# MCU.net
KiCad netlist of a schematic drawn in Altium Designer
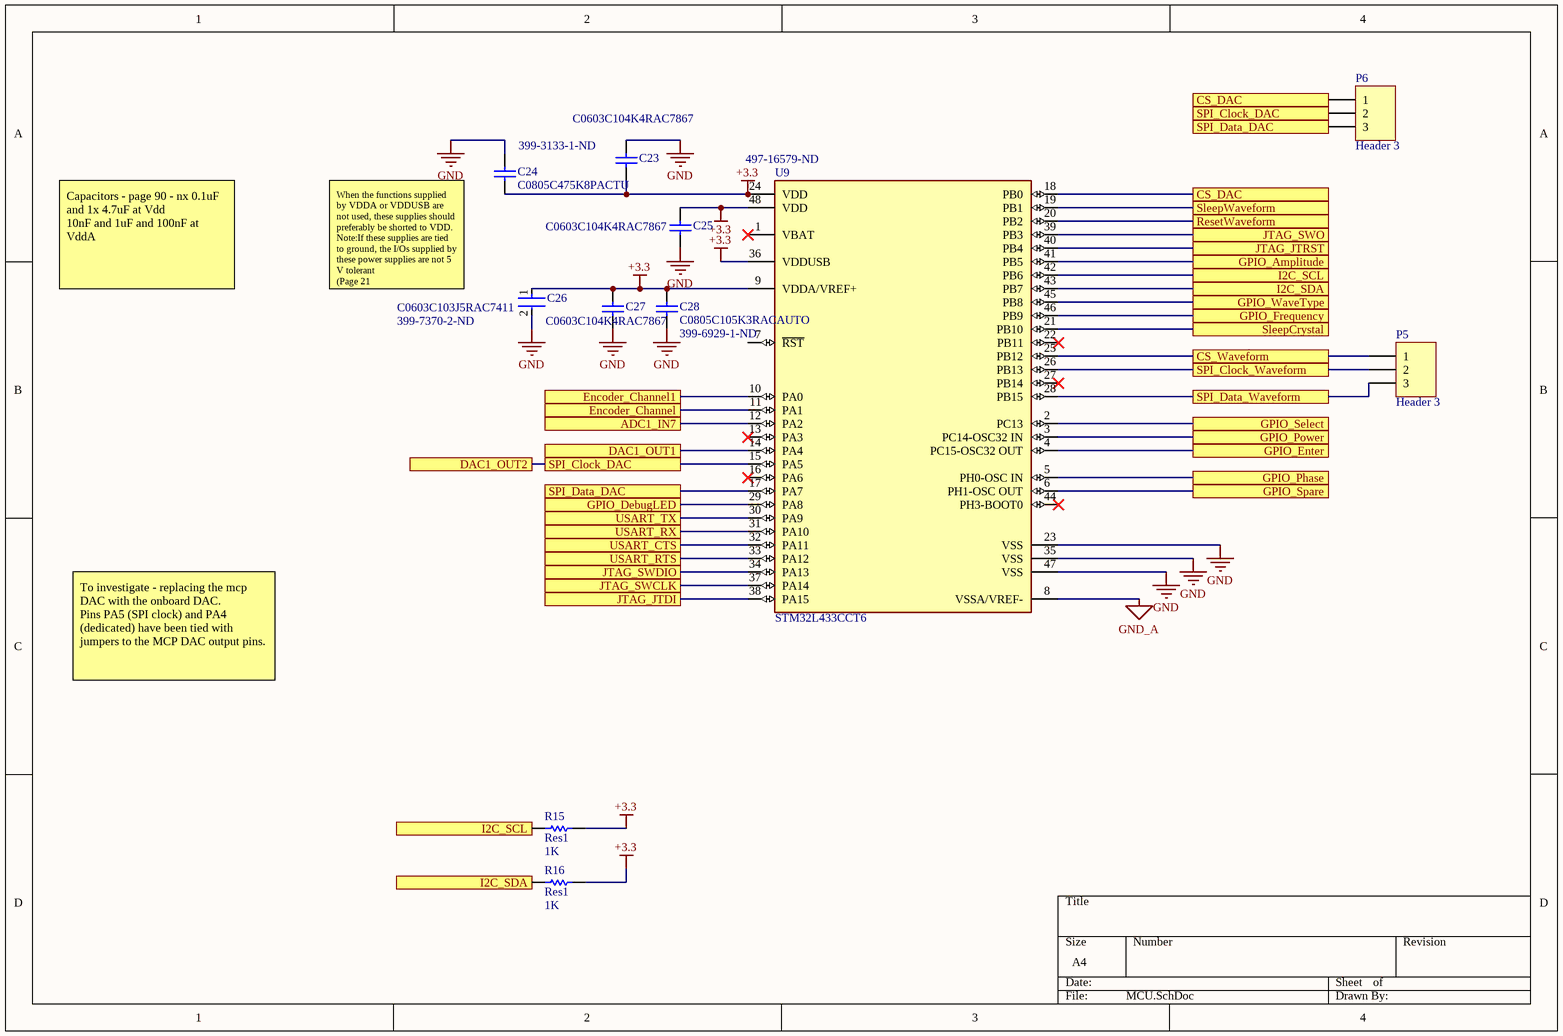
[diagram p0: MCU.SchDoc]

(export (version "E")
  (design (tool "Eeschema 10.0.6"))
  (components
    (comp (ref "C23")
      (value "C0603C104K4RAC7867")
      (footprint "CAPC1608X87X35NL15T15")
      (description "0.1uF Ceramic")
      (fields (field (name "MANUFACTURER") "Kemet") (field (name "TOLERANCE") "10%"))
      (libsource (lib "Altium Content Vault") (part "CAP"))
    )
    (comp (ref "C24")
      (value "C0805C475K8PACTU")
      (footprint "CAPC2013X145X50ML20T25")
      (fields
        (field (name "MANUFACTURER") "Kemet")
        (field (name "SUPPLIER PART NUMBER 1") "399-3133-1-ND")
        (field (name "TOLERANCE") "10%")
        (field (name "VOLTAGE") "10V")
      )
      (libsource (lib "Altium Content Vault") (part "CAP"))
    )
    (comp (ref "C25")
      (value "C0603C104K4RAC7867")
      (footprint "CAPC1608X87X35NL15T15")
      (description "0.1uF Ceramic")
      (fields (field (name "MANUFACTURER") "Kemet") (field (name "TOLERANCE") "10%"))
      (libsource (lib "Altium Content Vault") (part "CAP"))
    )
    (comp (ref "C26")
      (value "C0603C103J5RAC7411")
      (footprint "FP-C0603C-CF-MFG")
      (description "CAP CER 10000PF 50V X7R 0603")
      (fields
        (field (name "MANUFACTURER") "KEMET")
        (field (name "TOLERANCE") "0.05")
        (field (name "SUPPLIER PART NUMBER 1") "399-7370-2-ND")
      )
      (libsource (lib "Altium Content Vault") (part "b4654b650e69147ec39a6b967a45e02"))
    )
    (comp (ref "C27")
      (value "C0603C104K4RAC7867")
      (footprint "CAPC1608X87X35NL15T15")
      (description "0.1uF Ceramic")
      (fields (field (name "MANUFACTURER") "Kemet") (field (name "TOLERANCE") "10%"))
      (libsource (lib "Altium Content Vault") (part "CAP"))
    )
    (comp (ref "C28")
      (value "C0805C105K3RACAUTO")
      (footprint "CAPC2013X140X50ML20T25")
      (fields
        (field (name "MANUFACTURER") "Kemet")
        (field (name "SUPPLIER PART NUMBER 1") "399-6929-1-ND")
        (field (name "TOLERANCE") "10%")
      )
      (libsource (lib "Altium Content Vault") (part "CAP"))
    )
    (comp (ref "P5")
      (value "Header 3")
      (footprint "HDR1X3")
      (description "Header, 3-Pin")
      (fields (field (name "PUBLISHER") "Altium Limited"))
      (libsource (lib "Miscellaneous Connectors") (part "Header 3"))
    )
    (comp (ref "P6")
      (value "Header 3")
      (footprint "HDR1X3")
      (description "Header, 3-Pin")
      (fields (field (name "PUBLISHER") "Altium Limited"))
      (libsource (lib "Miscellaneous Connectors") (part "Header 3"))
    )
    (comp (ref "R15")
      (value "Res1")
      (footprint "AXIAL-0.3")
      (description "Resistor")
      (fields (field (name "ALTIUM_VALUE") "1K") (field (name "PUBLISHER") "Altium Limited"))
      (libsource (lib "Miscellaneous Devices") (part "Res1"))
    )
    (comp (ref "R16")
      (value "Res1")
      (footprint "AXIAL-0.3")
      (description "Resistor")
      (fields (field (name "ALTIUM_VALUE") "1K") (field (name "PUBLISHER") "Altium Limited"))
      (libsource (lib "Miscellaneous Devices") (part "Res1"))
    )
    (comp (ref "U9")
      (value "STM32L433CCT6")
      (footprint "FP-LQFP48-5B-MFG")
      (description "IC MCU 32BIT 256KB FLASH 48LQFP")
      (fields
        (field (name "MANUFACTURER") "STMicroelectronics")
        (field (name "OCTOPART") "https://octopart.com/stm32l433cct6-stmicroelectronics-71093511")
        (field (name "SUPPLIER PART NUMBER 1") "497-16579-ND")
      )
      (libsource (lib "Altium Content Vault") (part "174a8be184e27c1b29a4a816d407374"))
    )
  )
  (nets
    (net (code "1") (name "+3.3") (class "Default")
      (node (ref "C23") (pin "1") (pinfunction "1_1") (pintype "passive"))
      (node (ref "C24") (pin "1") (pinfunction "1_1") (pintype "passive"))
      (node (ref "C25") (pin "2") (pinfunction "2_2") (pintype "passive"))
      (node (ref "C26") (pin "1") (pinfunction "1_1") (pintype "passive"))
      (node (ref "C27") (pin "2") (pinfunction "2_2") (pintype "passive"))
      (node (ref "C28") (pin "2") (pinfunction "2_2") (pintype "passive"))
      (node (ref "R15") (pin "2") (pinfunction "2_2") (pintype "passive"))
      (node (ref "R16") (pin "2") (pinfunction "2_2") (pintype "passive"))
      (node (ref "U9") (pin "24") (pinfunction "VDD_24") (pintype "power_in"))
      (node (ref "U9") (pin "36") (pinfunction "VDDUSB_36") (pintype "power_in"))
      (node (ref "U9") (pin "48") (pinfunction "VDD_48") (pintype "power_in"))
      (node (ref "U9") (pin "9") (pinfunction "VDDA/VREF+_9") (pintype "power_in"))
    )
    (net (code "2") (name "/ADC1_IN7") (class "Default")
      (node (ref "U9") (pin "12") (pinfunction "PA2_12") (pintype "bidirectional"))
    )
    (net (code "3") (name "/CS_DAC") (class "Default")
      (node (ref "P6") (pin "1") (pinfunction "1_1") (pintype "passive"))
      (node (ref "U9") (pin "18") (pinfunction "PB0_18") (pintype "bidirectional"))
    )
    (net (code "4") (name "/CS_Waveform") (class "Default")
      (node (ref "P5") (pin "1") (pinfunction "1_1") (pintype "passive"))
      (node (ref "U9") (pin "25") (pinfunction "PB12_25") (pintype "bidirectional"))
    )
    (net (code "5") (name "/DAC1_OUT1") (class "Default")
      (node (ref "U9") (pin "14") (pinfunction "PA4_14") (pintype "bidirectional"))
    )
    (net (code "6") (name "/DAC1_OUT2") (class "Default")
      (node (ref "P6") (pin "2") (pinfunction "2_2") (pintype "passive"))
      (node (ref "U9") (pin "15") (pinfunction "PA5_15") (pintype "bidirectional"))
    )
    (net (code "7") (name "/Encoder_Channel") (class "Default")
      (node (ref "U9") (pin "11") (pinfunction "PA1_11") (pintype "bidirectional"))
    )
    (net (code "8") (name "/Encoder_Channel1") (class "Default")
      (node (ref "U9") (pin "10") (pinfunction "PA0_10") (pintype "bidirectional"))
    )
    (net (code "9") (name "/GPIO_Amplitude") (class "Default")
      (node (ref "U9") (pin "41") (pinfunction "PB5_41") (pintype "bidirectional"))
    )
    (net (code "10") (name "/GPIO_DebugLED") (class "Default")
      (node (ref "U9") (pin "29") (pinfunction "PA8_29") (pintype "bidirectional"))
    )
    (net (code "11") (name "/GPIO_Enter") (class "Default")
      (node (ref "U9") (pin "4") (pinfunction "PC15-OSC32_OUT_4") (pintype "bidirectional"))
    )
    (net (code "12") (name "/GPIO_Frequency") (class "Default")
      (node (ref "U9") (pin "46") (pinfunction "PB9_46") (pintype "bidirectional"))
    )
    (net (code "13") (name "/GPIO_Phase") (class "Default")
      (node (ref "U9") (pin "5") (pinfunction "PH0-OSC_IN_5") (pintype "bidirectional"))
    )
    (net (code "14") (name "/GPIO_Power") (class "Default")
      (node (ref "U9") (pin "3") (pinfunction "PC14-OSC32_IN_3") (pintype "bidirectional"))
    )
    (net (code "15") (name "/GPIO_Select") (class "Default")
      (node (ref "U9") (pin "2") (pinfunction "PC13_2") (pintype "bidirectional"))
    )
    (net (code "16") (name "/GPIO_Spare") (class "Default")
      (node (ref "U9") (pin "6") (pinfunction "PH1-OSC_OUT_6") (pintype "bidirectional"))
    )
    (net (code "17") (name "/GPIO_WaveType") (class "Default")
      (node (ref "U9") (pin "45") (pinfunction "PB8_45") (pintype "bidirectional"))
    )
    (net (code "18") (name "/I2C_SCL") (class "Default")
      (node (ref "R15") (pin "1") (pinfunction "1_1") (pintype "passive"))
      (node (ref "U9") (pin "42") (pinfunction "PB6_42") (pintype "bidirectional"))
    )
    (net (code "19") (name "/I2C_SDA") (class "Default")
      (node (ref "R16") (pin "1") (pinfunction "1_1") (pintype "passive"))
      (node (ref "U9") (pin "43") (pinfunction "PB7_43") (pintype "bidirectional"))
    )
    (net (code "20") (name "/JTAG_JTDI") (class "Default")
      (node (ref "U9") (pin "38") (pinfunction "PA15_38") (pintype "bidirectional"))
    )
    (net (code "21") (name "/JTAG_JTRST") (class "Default")
      (node (ref "U9") (pin "40") (pinfunction "PB4_40") (pintype "bidirectional"))
    )
    (net (code "22") (name "/JTAG_SWCLK") (class "Default")
      (node (ref "U9") (pin "37") (pinfunction "PA14_37") (pintype "bidirectional"))
    )
    (net (code "23") (name "/JTAG_SWDIO") (class "Default")
      (node (ref "U9") (pin "34") (pinfunction "PA13_34") (pintype "bidirectional"))
    )
    (net (code "24") (name "/JTAG_SWO") (class "Default")
      (node (ref "U9") (pin "39") (pinfunction "PB3_39") (pintype "bidirectional"))
    )
    (net (code "25") (name "/ResetWaveform") (class "Default")
      (node (ref "U9") (pin "20") (pinfunction "PB2_20") (pintype "bidirectional"))
    )
    (net (code "26") (name "/SPI_Clock_Waveform") (class "Default")
      (node (ref "P5") (pin "2") (pinfunction "2_2") (pintype "passive"))
      (node (ref "U9") (pin "26") (pinfunction "PB13_26") (pintype "bidirectional"))
    )
    (net (code "27") (name "/SPI_Data_DAC") (class "Default")
      (node (ref "P6") (pin "3") (pinfunction "3_3") (pintype "passive"))
      (node (ref "U9") (pin "17") (pinfunction "PA7_17") (pintype "bidirectional"))
    )
    (net (code "28") (name "/SPI_Data_Waveform") (class "Default")
      (node (ref "P5") (pin "3") (pinfunction "3_3") (pintype "passive"))
      (node (ref "U9") (pin "28") (pinfunction "PB15_28") (pintype "bidirectional"))
    )
    (net (code "29") (name "/SleepCrystal") (class "Default")
      (node (ref "U9") (pin "21") (pinfunction "PB10_21") (pintype "bidirectional"))
    )
    (net (code "30") (name "/SleepWaveform") (class "Default")
      (node (ref "U9") (pin "19") (pinfunction "PB1_19") (pintype "bidirectional"))
    )
    (net (code "31") (name "/USART_CTS") (class "Default")
      (node (ref "U9") (pin "32") (pinfunction "PA11_32") (pintype "bidirectional"))
    )
    (net (code "32") (name "/USART_RTS") (class "Default")
      (node (ref "U9") (pin "33") (pinfunction "PA12_33") (pintype "bidirectional"))
    )
    (net (code "33") (name "/USART_RX") (class "Default")
      (node (ref "U9") (pin "31") (pinfunction "PA10_31") (pintype "bidirectional"))
    )
    (net (code "34") (name "/USART_TX") (class "Default")
      (node (ref "U9") (pin "30") (pinfunction "PA9_30") (pintype "bidirectional"))
    )
    (net (code "35") (name "GND") (class "Default")
      (node (ref "C23") (pin "2") (pinfunction "2_2") (pintype "passive"))
      (node (ref "C24") (pin "2") (pinfunction "2_2") (pintype "passive"))
      (node (ref "C25") (pin "1") (pinfunction "1_1") (pintype "passive"))
      (node (ref "C26") (pin "2") (pinfunction "2_2") (pintype "passive"))
      (node (ref "C27") (pin "1") (pinfunction "1_1") (pintype "passive"))
      (node (ref "C28") (pin "1") (pinfunction "1_1") (pintype "passive"))
      (node (ref "U9") (pin "23") (pinfunction "VSS_23") (pintype "power_in"))
      (node (ref "U9") (pin "35") (pinfunction "VSS_35") (pintype "power_in"))
      (node (ref "U9") (pin "47") (pinfunction "VSS_47") (pintype "power_in"))
    )
    (net (code "36") (name "GND_A") (class "Default")
      (node (ref "U9") (pin "8") (pinfunction "VSSA/VREF-_8") (pintype "power_in"))
    )
    (net (code "37") (name "unconnected-(U9-PA3-Pad13)") (class "Default")
      (node (ref "U9") (pin "13") (pinfunction "PA3_13") (pintype "bidirectional+no_connect"))
    )
    (net (code "38") (name "unconnected-(U9-PA6-Pad16)") (class "Default")
      (node (ref "U9") (pin "16") (pinfunction "PA6_16") (pintype "bidirectional+no_connect"))
    )
    (net (code "39") (name "unconnected-(U9-PB11-Pad22)") (class "Default")
      (node (ref "U9") (pin "22") (pinfunction "PB11_22") (pintype "bidirectional+no_connect"))
    )
    (net (code "40") (name "unconnected-(U9-PB14-Pad27)") (class "Default")
      (node (ref "U9") (pin "27") (pinfunction "PB14_27") (pintype "bidirectional+no_connect"))
    )
    (net (code "41") (name "unconnected-(U9-PH3-BOOT0-Pad44)") (class "Default")
      (node (ref "U9") (pin "44") (pinfunction "PH3-BOOT0_44") (pintype "bidirectional+no_connect"))
    )
    (net (code "42") (name "unconnected-(U9-VBAT-Pad1)") (class "Default")
      (node (ref "U9") (pin "1") (pinfunction "VBAT_1") (pintype "power_in+no_connect"))
    )
    (net (code "43") (name "unconnected-(U9-~{RST}-Pad7)") (class "Default")
      (node (ref "U9") (pin "7") (pinfunction "~{RST}_7") (pintype "bidirectional"))
    )
  )
)
